# sensordrone_audio_jack.net
KiCad netlist of a schematic drawn in EAGLE
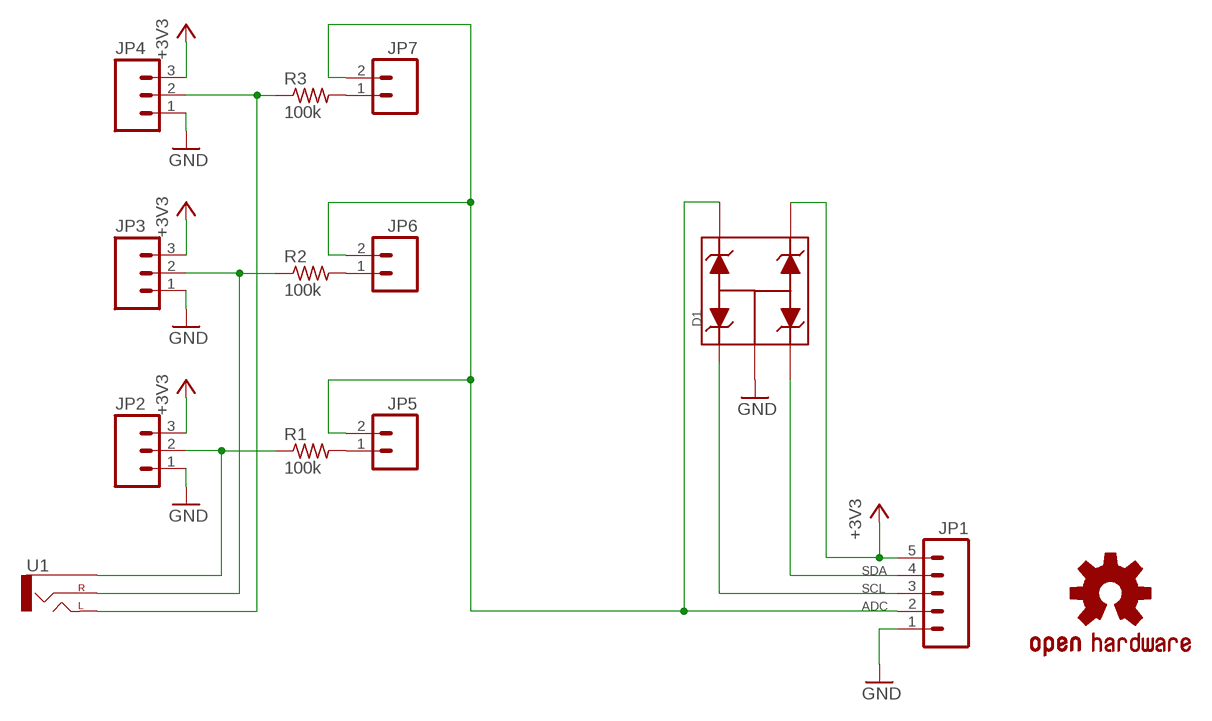
[diagram p0: schematic, sheet 1]

(export (version "E")
  (design (tool "Eeschema 10.0.6"))
  (components
    (comp (ref "D1")
      (value "CPDV5")
      (footprint "eagle-import:SOT353")
      (libsource (lib "eagle-import") (part "CPDV5"))
    )
    (comp (ref "JP1")
      (value "M05PTH_LONGPADS")
      (footprint "eagle-import:1X05_LONGPADS")
      (libsource (lib "eagle-import") (part "M05PTH_LONGPADS"))
    )
    (comp (ref "JP2")
      (value "M03PTH")
      (footprint "eagle-import:1X03")
      (libsource (lib "eagle-import") (part "M03PTH"))
    )
    (comp (ref "JP3")
      (value "M03PTH")
      (footprint "eagle-import:1X03")
      (libsource (lib "eagle-import") (part "M03PTH"))
    )
    (comp (ref "JP4")
      (value "M03PTH")
      (footprint "eagle-import:1X03")
      (libsource (lib "eagle-import") (part "M03PTH"))
    )
    (comp (ref "JP5")
      (value "M02PTH")
      (footprint "eagle-import:1X02")
      (libsource (lib "eagle-import") (part "M02PTH"))
    )
    (comp (ref "JP6")
      (value "M02PTH")
      (footprint "eagle-import:1X02")
      (libsource (lib "eagle-import") (part "M02PTH"))
    )
    (comp (ref "JP7")
      (value "M02PTH")
      (footprint "eagle-import:1X02")
      (libsource (lib "eagle-import") (part "M02PTH"))
    )
    (comp (ref "R1")
      (value "100k")
      (footprint "eagle-import:R0402")
      (libsource (lib "eagle-import") (part "R-US_R0402"))
    )
    (comp (ref "R2")
      (value "100k")
      (footprint "eagle-import:R0402")
      (libsource (lib "eagle-import") (part "R-US_R0402"))
    )
    (comp (ref "R3")
      (value "100k")
      (footprint "eagle-import:R0402")
      (libsource (lib "eagle-import") (part "R-US_R0402"))
    )
    (comp (ref "U$1")
      (value "OSHW-LOGOS")
      (footprint "eagle-import:OSHW-LOGO-S")
      (libsource (lib "eagle-import") (part "OSHW-LOGOS"))
    )
    (comp (ref "U1")
      (value "AUDIO-JACKPTH")
      (footprint "eagle-import:AUDIO-JACK")
      (libsource (lib "eagle-import") (part "AUDIO-JACKPTH"))
    )
  )
  (nets
    (net (code "1") (name "+3V3") (class "Default")
      (node (ref "D1") (pin "4") (pinfunction "P$4_4") (pintype "bidirectional"))
      (node (ref "JP1") (pin "5") (pinfunction "5_5") (pintype "passive"))
      (node (ref "JP2") (pin "3") (pinfunction "3_3") (pintype "passive"))
      (node (ref "JP3") (pin "3") (pinfunction "3_3") (pintype "passive"))
      (node (ref "JP4") (pin "3") (pinfunction "3_3") (pintype "passive"))
    )
    (net (code "2") (name "/ADC") (class "Default")
      (node (ref "D1") (pin "5") (pinfunction "P$5_5") (pintype "bidirectional"))
      (node (ref "JP1") (pin "2") (pinfunction "2_2") (pintype "passive"))
      (node (ref "JP5") (pin "2") (pinfunction "2_2") (pintype "passive"))
      (node (ref "JP6") (pin "2") (pinfunction "2_2") (pintype "passive"))
      (node (ref "JP7") (pin "2") (pinfunction "2_2") (pintype "passive"))
    )
    (net (code "3") (name "/SCL") (class "Default")
      (node (ref "D1") (pin "1") (pinfunction "P$1_1") (pintype "bidirectional"))
      (node (ref "JP1") (pin "3") (pinfunction "3_3") (pintype "passive"))
    )
    (net (code "4") (name "/SDA") (class "Default")
      (node (ref "D1") (pin "3") (pinfunction "P$3_3") (pintype "bidirectional"))
      (node (ref "JP1") (pin "4") (pinfunction "4_4") (pintype "passive"))
    )
    (net (code "5") (name "GND") (class "Default")
      (node (ref "D1") (pin "2") (pinfunction "P$2_2") (pintype "bidirectional"))
      (node (ref "JP1") (pin "1") (pinfunction "1_1") (pintype "passive"))
      (node (ref "JP2") (pin "1") (pinfunction "1_1") (pintype "passive"))
      (node (ref "JP3") (pin "1") (pinfunction "1_1") (pintype "passive"))
      (node (ref "JP4") (pin "1") (pinfunction "1_1") (pintype "passive"))
    )
    (net (code "6") (name "Net-(JP2-Pad2)") (class "Default")
      (node (ref "JP2") (pin "2") (pinfunction "2_2") (pintype "passive"))
      (node (ref "R1") (pin "1") (pinfunction "1_1") (pintype "passive"))
      (node (ref "U1") (pin "SLEEVE") (pinfunction "SLEEVE_SLEEVE") (pintype "bidirectional"))
    )
    (net (code "7") (name "Net-(JP5-Pad1)") (class "Default")
      (node (ref "JP5") (pin "1") (pinfunction "1_1") (pintype "passive"))
      (node (ref "R1") (pin "2") (pinfunction "2_2") (pintype "passive"))
    )
    (net (code "8") (name "Net-(JP6-Pad1)") (class "Default")
      (node (ref "JP6") (pin "1") (pinfunction "1_1") (pintype "passive"))
      (node (ref "R2") (pin "2") (pinfunction "2_2") (pintype "passive"))
    )
    (net (code "9") (name "Net-(JP7-Pad1)") (class "Default")
      (node (ref "JP7") (pin "1") (pinfunction "1_1") (pintype "passive"))
      (node (ref "R3") (pin "2") (pinfunction "2_2") (pintype "passive"))
    )
    (net (code "10") (name "Net-(U1-LEFT)") (class "Default")
      (node (ref "JP4") (pin "2") (pinfunction "2_2") (pintype "passive"))
      (node (ref "R3") (pin "1") (pinfunction "1_1") (pintype "passive"))
      (node (ref "U1") (pin "TIP") (pinfunction "LEFT_TIP") (pintype "bidirectional"))
    )
    (net (code "11") (name "Net-(U1-RIGHT)") (class "Default")
      (node (ref "JP3") (pin "2") (pinfunction "2_2") (pintype "passive"))
      (node (ref "R2") (pin "1") (pinfunction "1_1") (pintype "passive"))
      (node (ref "U1") (pin "RING") (pinfunction "RIGHT_RING") (pintype "bidirectional"))
    )
  )
)
